# houz_bedroom.net
KiCad netlist of a schematic drawn in EAGLE
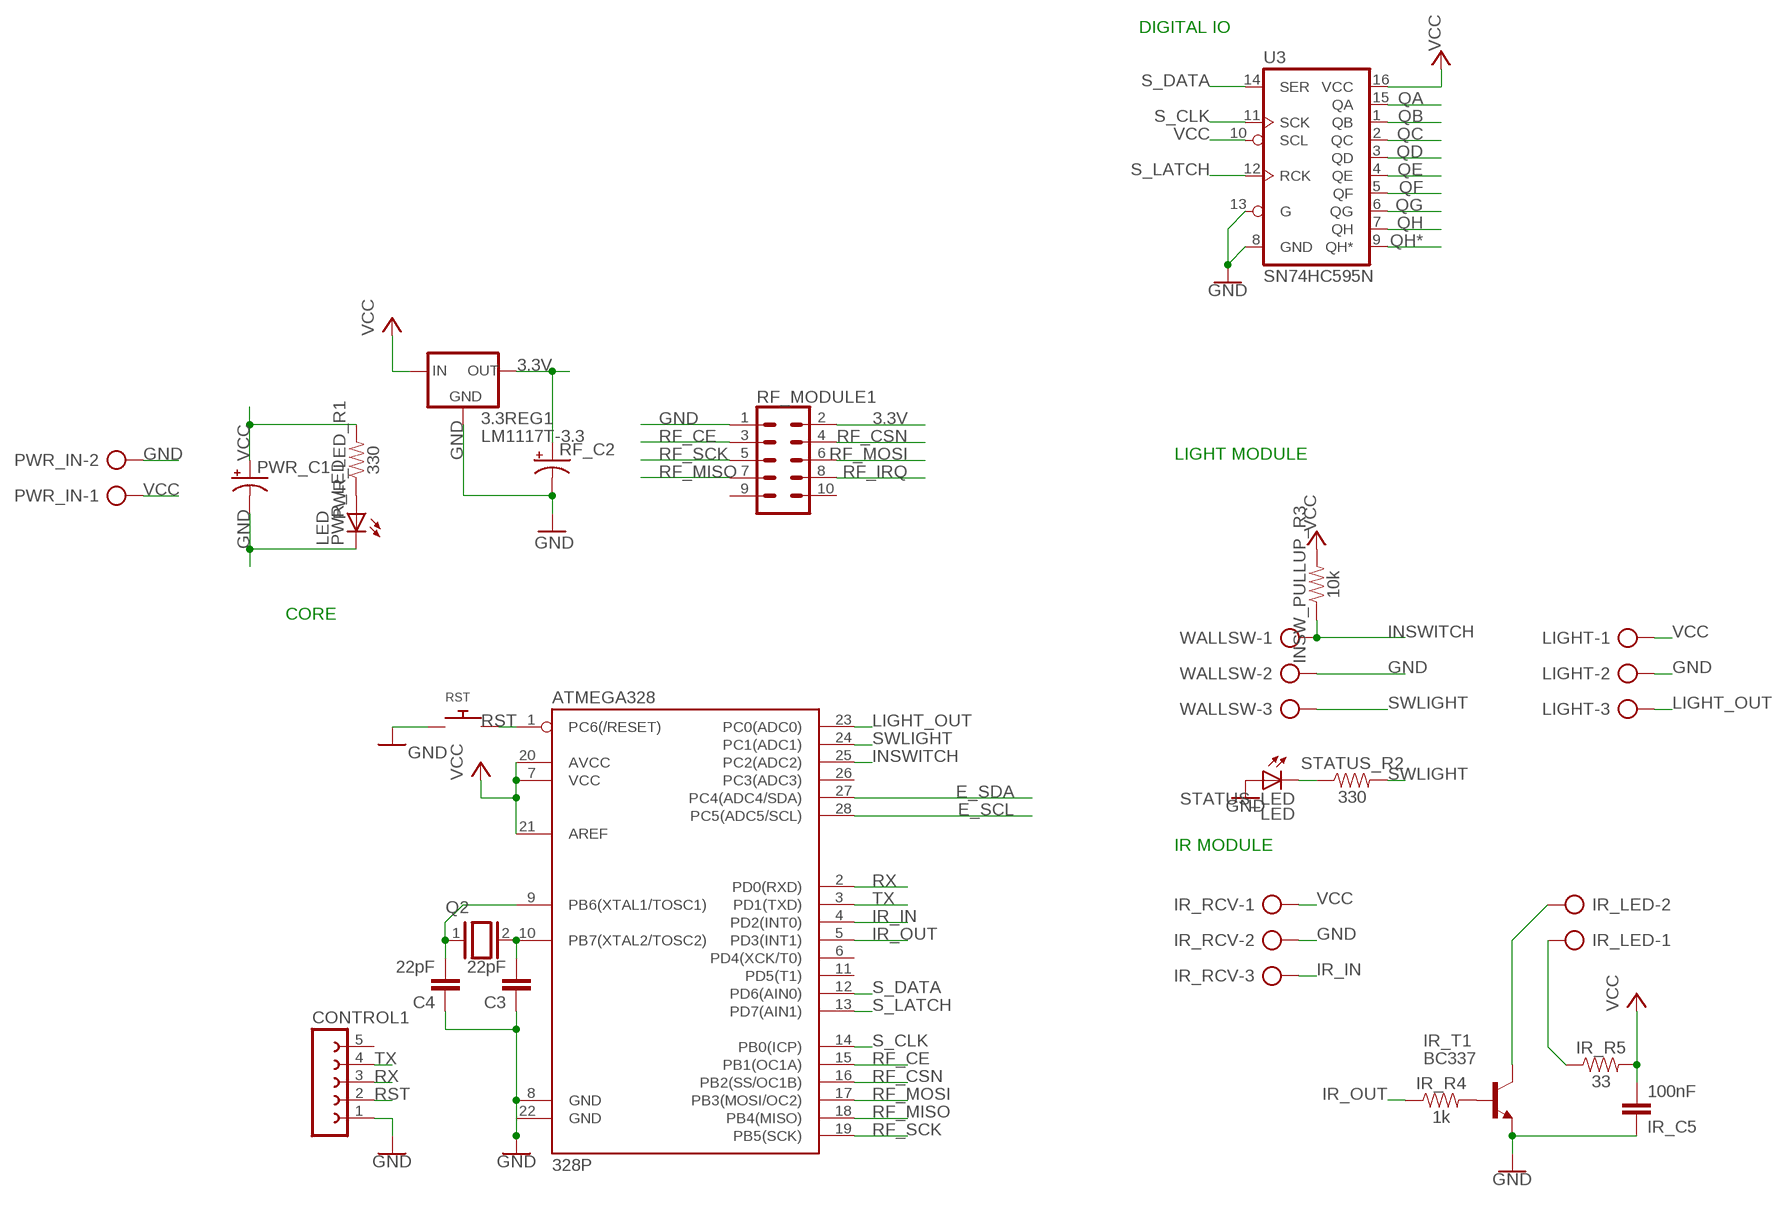
[diagram p0: schematic, sheet 1]

(export (version "E")
  (design (tool "Eeschema 10.0.6"))
  (components
    (comp (ref "3.3REG1")
      (value "LM1117T-3.3")
      (footprint "eagle-import:TO220")
      (libsource (lib "eagle-import") (part "LM1117T-3.3"))
    )
    (comp (ref "ATMEGA328")
      (value "328P")
      (footprint "eagle-import:DIP28")
      (libsource (lib "eagle-import") (part "ATMEGA328P_PDIP"))
    )
    (comp (ref "C3")
      (value "22pF")
      (footprint "eagle-import:C050-030X075")
      (libsource (lib "eagle-import") (part "C-EU050-030X075"))
    )
    (comp (ref "C4")
      (value "22pF")
      (footprint "eagle-import:C050-030X075")
      (libsource (lib "eagle-import") (part "C-EU050-030X075"))
    )
    (comp (ref "CONTROL1")
      (value "FE05-1")
      (footprint "eagle-import:FE05-1")
      (libsource (lib "eagle-import") (part "FE05-1"))
    )
    (comp (ref "INSW_PULLUP_R3")
      (value "10k")
      (footprint "eagle-import:AXIAL-0.3")
      (libsource (lib "eagle-import") (part "RESISTORAXIAL-0.3"))
    )
    (comp (ref "IR_C5")
      (value "100nF")
      (footprint "eagle-import:C050-030X075")
      (libsource (lib "eagle-import") (part "C-EU050-030X075"))
    )
    (comp (ref "IR_LED")
      (value "AK500/2-H")
      (footprint "eagle-import:AK500_2-H")
      (libsource (lib "eagle-import") (part "AK500/2-H"))
    )
    (comp (ref "IR_R4")
      (value "1k")
      (footprint "eagle-import:AXIAL-0.3")
      (libsource (lib "eagle-import") (part "RESISTORAXIAL-0.3"))
    )
    (comp (ref "IR_R5")
      (value "33")
      (footprint "eagle-import:AXIAL-0.3")
      (libsource (lib "eagle-import") (part "RESISTORAXIAL-0.3"))
    )
    (comp (ref "IR_RCV")
      (value "AK500/3")
      (footprint "eagle-import:AK500_3")
      (libsource (lib "eagle-import") (part "AK500/3"))
    )
    (comp (ref "IR_T1")
      (value "BC337")
      (footprint "eagle-import:TO92")
      (libsource (lib "eagle-import") (part "BC337"))
    )
    (comp (ref "LIGHT")
      (value "AK500/3")
      (footprint "eagle-import:AK500_3")
      (libsource (lib "eagle-import") (part "AK500/3"))
    )
    (comp (ref "PWR_C1")
      (value "CPOL-USE7.5-16")
      (footprint "eagle-import:E7,5-16")
      (libsource (lib "eagle-import") (part "CPOL-USE7.5-16"))
    )
    (comp (ref "PWR_IN")
      (value "AK500/2-H")
      (footprint "eagle-import:AK500_2-H")
      (libsource (lib "eagle-import") (part "AK500/2-H"))
    )
    (comp (ref "PWR_LED")
      (value "LED")
      (footprint "eagle-import:LED3MM")
      (libsource (lib "eagle-import") (part "LED3MM"))
    )
    (comp (ref "PWR_LED_R1")
      (value "330")
      (footprint "eagle-import:AXIAL-0.3")
      (libsource (lib "eagle-import") (part "RESISTORAXIAL-0.3"))
    )
    (comp (ref "Q2")
      (value "16MHz")
      (footprint "eagle-import:QS")
      (libsource (lib "eagle-import") (part "XTAL/S"))
    )
    (comp (ref "RF_C2")
      (value "CPOL-USE5-10.5")
      (footprint "eagle-import:E5-10,5")
      (libsource (lib "eagle-import") (part "CPOL-USE5-10.5"))
    )
    (comp (ref "RF_MODULE1")
      (value "CONN_05X2NO_SILK")
      (footprint "eagle-import:2X5_NOSILK")
      (libsource (lib "eagle-import") (part "CONN_05X2NO_SILK"))
    )
    (comp (ref "RST")
      (value "SWITCH_PUSHBUTTONEVQ-PE")
      (footprint "eagle-import:TACT_PANA-EVQ")
      (libsource (lib "eagle-import") (part "SWITCH_PUSHBUTTONEVQ-PE"))
    )
    (comp (ref "STATUS_LED")
      (value "LED")
      (footprint "eagle-import:LED3MM")
      (libsource (lib "eagle-import") (part "LED3MM"))
    )
    (comp (ref "STATUS_R2")
      (value "330")
      (footprint "eagle-import:AXIAL-0.3")
      (libsource (lib "eagle-import") (part "RESISTORAXIAL-0.3"))
    )
    (comp (ref "U3")
      (value "SN74HC595N")
      (footprint "eagle-import:DIP16")
      (libsource (lib "eagle-import") (part "74595NHC"))
    )
    (comp (ref "WALLSW")
      (value "AK500/3")
      (footprint "eagle-import:AK500_3")
      (libsource (lib "eagle-import") (part "AK500/3"))
    )
  )
  (nets
    (net (code "1") (name "/3.3V") (class "Default")
      (node (ref "3.3REG1") (pin "2") (pinfunction "OUT_2") (pintype "passive"))
      (node (ref "RF_C2") (pin "+") (pinfunction "+_+") (pintype "passive"))
      (node (ref "RF_MODULE1") (pin "2") (pinfunction "2_2") (pintype "passive"))
    )
    (net (code "2") (name "/E_SCL") (class "Default")
      (node (ref "ATMEGA328") (pin "28") (pinfunction "PC5(ADC5/SCL)_28") (pintype "bidirectional"))
    )
    (net (code "3") (name "/E_SDA") (class "Default")
      (node (ref "ATMEGA328") (pin "27") (pinfunction "PC4(ADC4/SDA)_27") (pintype "bidirectional"))
    )
    (net (code "4") (name "/INSWITCH") (class "Default")
      (node (ref "ATMEGA328") (pin "25") (pinfunction "PC2(ADC2)_25") (pintype "bidirectional"))
      (node (ref "INSW_PULLUP_R3") (pin "P$1") (pinfunction "1_P$1") (pintype "passive"))
      (node (ref "WALLSW") (pin "1") (pinfunction "KL_1") (pintype "passive"))
    )
    (net (code "5") (name "/IR_IN") (class "Default")
      (node (ref "ATMEGA328") (pin "4") (pinfunction "PD2(INT0)_4") (pintype "bidirectional"))
      (node (ref "IR_RCV") (pin "3") (pinfunction "KL_3") (pintype "passive"))
    )
    (net (code "6") (name "/IR_OUT") (class "Default")
      (node (ref "ATMEGA328") (pin "5") (pinfunction "PD3(INT1)_5") (pintype "bidirectional"))
      (node (ref "IR_R4") (pin "P$1") (pinfunction "1_P$1") (pintype "passive"))
    )
    (net (code "7") (name "/LIGHT_OUT") (class "Default")
      (node (ref "ATMEGA328") (pin "23") (pinfunction "PC0(ADC0)_23") (pintype "bidirectional"))
      (node (ref "LIGHT") (pin "3") (pinfunction "KL_3") (pintype "passive"))
    )
    (net (code "8") (name "/QA") (class "Default")
      (node (ref "U3") (pin "15") (pinfunction "QA_15") (pintype "tri_state"))
    )
    (net (code "9") (name "/QB") (class "Default")
      (node (ref "U3") (pin "1") (pinfunction "QB_1") (pintype "tri_state"))
    )
    (net (code "10") (name "/QC") (class "Default")
      (node (ref "U3") (pin "2") (pinfunction "QC_2") (pintype "tri_state"))
    )
    (net (code "11") (name "/QD") (class "Default")
      (node (ref "U3") (pin "3") (pinfunction "QD_3") (pintype "tri_state"))
    )
    (net (code "12") (name "/QE") (class "Default")
      (node (ref "U3") (pin "4") (pinfunction "QE_4") (pintype "tri_state"))
    )
    (net (code "13") (name "/QF") (class "Default")
      (node (ref "U3") (pin "5") (pinfunction "QF_5") (pintype "tri_state"))
    )
    (net (code "14") (name "/QG") (class "Default")
      (node (ref "U3") (pin "6") (pinfunction "QG_6") (pintype "tri_state"))
    )
    (net (code "15") (name "/QH") (class "Default")
      (node (ref "U3") (pin "7") (pinfunction "QH_7") (pintype "tri_state"))
    )
    (net (code "16") (name "/QH*") (class "Default")
      (node (ref "U3") (pin "9") (pinfunction "QH*_9") (pintype "tri_state"))
    )
    (net (code "17") (name "/RF_CE") (class "Default")
      (node (ref "ATMEGA328") (pin "15") (pinfunction "PB1(OC1A)_15") (pintype "bidirectional"))
      (node (ref "RF_MODULE1") (pin "3") (pinfunction "3_3") (pintype "passive"))
    )
    (net (code "18") (name "/RF_CSN") (class "Default")
      (node (ref "ATMEGA328") (pin "16") (pinfunction "PB2(SS/OC1B)_16") (pintype "bidirectional"))
      (node (ref "RF_MODULE1") (pin "4") (pinfunction "4_4") (pintype "passive"))
    )
    (net (code "19") (name "/RF_IRQ") (class "Default")
      (node (ref "RF_MODULE1") (pin "8") (pinfunction "8_8") (pintype "passive"))
    )
    (net (code "20") (name "/RF_MISO") (class "Default")
      (node (ref "ATMEGA328") (pin "18") (pinfunction "PB4(MISO)_18") (pintype "bidirectional"))
      (node (ref "RF_MODULE1") (pin "7") (pinfunction "7_7") (pintype "passive"))
    )
    (net (code "21") (name "/RF_MOSI") (class "Default")
      (node (ref "ATMEGA328") (pin "17") (pinfunction "PB3(MOSI/OC2)_17") (pintype "bidirectional"))
      (node (ref "RF_MODULE1") (pin "6") (pinfunction "6_6") (pintype "passive"))
    )
    (net (code "22") (name "/RF_SCK") (class "Default")
      (node (ref "ATMEGA328") (pin "19") (pinfunction "PB5(SCK)_19") (pintype "bidirectional"))
      (node (ref "RF_MODULE1") (pin "5") (pinfunction "5_5") (pintype "passive"))
    )
    (net (code "23") (name "/RST") (class "Default")
      (node (ref "ATMEGA328") (pin "1") (pinfunction "PC6(/RESET)_1") (pintype "bidirectional"))
      (node (ref "CONTROL1") (pin "2") (pinfunction "2_2") (pintype "passive"))
      (node (ref "RST") (pin "P$2") (pinfunction "P$2_P$2") (pintype "passive"))
    )
    (net (code "24") (name "/RX") (class "Default")
      (node (ref "ATMEGA328") (pin "2") (pinfunction "PD0(RXD)_2") (pintype "bidirectional"))
      (node (ref "CONTROL1") (pin "3") (pinfunction "3_3") (pintype "passive"))
    )
    (net (code "25") (name "/SWLIGHT") (class "Default")
      (node (ref "ATMEGA328") (pin "24") (pinfunction "PC1(ADC1)_24") (pintype "bidirectional"))
      (node (ref "STATUS_R2") (pin "P$2") (pinfunction "2_P$2") (pintype "passive"))
      (node (ref "WALLSW") (pin "3") (pinfunction "KL_3") (pintype "passive"))
    )
    (net (code "26") (name "/S_CLK") (class "Default")
      (node (ref "ATMEGA328") (pin "14") (pinfunction "PB0(ICP)_14") (pintype "bidirectional"))
      (node (ref "U3") (pin "11") (pinfunction "SCK_11") (pintype "input"))
    )
    (net (code "27") (name "/S_DATA") (class "Default")
      (node (ref "ATMEGA328") (pin "12") (pinfunction "PD6(AIN0)_12") (pintype "bidirectional"))
      (node (ref "U3") (pin "14") (pinfunction "SER_14") (pintype "input"))
    )
    (net (code "28") (name "/S_LATCH") (class "Default")
      (node (ref "ATMEGA328") (pin "13") (pinfunction "PD7(AIN1)_13") (pintype "bidirectional"))
      (node (ref "U3") (pin "12") (pinfunction "RCK_12") (pintype "input"))
    )
    (net (code "29") (name "/TX") (class "Default")
      (node (ref "ATMEGA328") (pin "3") (pinfunction "PD1(TXD)_3") (pintype "bidirectional"))
      (node (ref "CONTROL1") (pin "4") (pinfunction "4_4") (pintype "passive"))
    )
    (net (code "30") (name "GND") (class "Default")
      (node (ref "3.3REG1") (pin "1") (pinfunction "GND_1") (pintype "input"))
      (node (ref "ATMEGA328") (pin "22") (pinfunction "GND_22") (pintype "bidirectional"))
      (node (ref "ATMEGA328") (pin "8") (pinfunction "GND_8") (pintype "bidirectional"))
      (node (ref "C3") (pin "1") (pinfunction "1_1") (pintype "passive"))
      (node (ref "C4") (pin "1") (pinfunction "1_1") (pintype "passive"))
      (node (ref "CONTROL1") (pin "1") (pinfunction "1_1") (pintype "passive"))
      (node (ref "IR_C5") (pin "1") (pinfunction "1_1") (pintype "passive"))
      (node (ref "IR_RCV") (pin "2") (pinfunction "KL_2") (pintype "passive"))
      (node (ref "IR_T1") (pin "1") (pinfunction "E_1") (pintype "passive"))
      (node (ref "LIGHT") (pin "2") (pinfunction "KL_2") (pintype "passive"))
      (node (ref "PWR_C1") (pin "-") (pinfunction "-_-") (pintype "passive"))
      (node (ref "PWR_IN") (pin "2") (pinfunction "KL_2") (pintype "passive"))
      (node (ref "PWR_LED") (pin "K") (pinfunction "C_K") (pintype "passive"))
      (node (ref "RF_C2") (pin "-") (pinfunction "-_-") (pintype "passive"))
      (node (ref "RF_MODULE1") (pin "1") (pinfunction "1_1") (pintype "passive"))
      (node (ref "RST") (pin "P$1") (pinfunction "P$1_P$1") (pintype "passive"))
      (node (ref "STATUS_LED") (pin "A") (pinfunction "A_A") (pintype "passive"))
      (node (ref "U3") (pin "13") (pinfunction "G_13") (pintype "input"))
      (node (ref "U3") (pin "8") (pinfunction "GND_8") (pintype "power_in"))
      (node (ref "WALLSW") (pin "2") (pinfunction "KL_2") (pintype "passive"))
    )
    (net (code "31") (name "Net-(ATMEGA328-PB6(XTAL1{slash}TOSC1))") (class "Default")
      (node (ref "ATMEGA328") (pin "9") (pinfunction "PB6(XTAL1/TOSC1)_9") (pintype "bidirectional"))
      (node (ref "C4") (pin "2") (pinfunction "2_2") (pintype "passive"))
      (node (ref "Q2") (pin "1") (pinfunction "1_1") (pintype "passive"))
    )
    (net (code "32") (name "Net-(ATMEGA328-PB7(XTAL2{slash}TOSC2))") (class "Default")
      (node (ref "ATMEGA328") (pin "10") (pinfunction "PB7(XTAL2/TOSC2)_10") (pintype "bidirectional"))
      (node (ref "C3") (pin "2") (pinfunction "2_2") (pintype "passive"))
      (node (ref "Q2") (pin "2") (pinfunction "2_2") (pintype "passive"))
    )
    (net (code "33") (name "Net-(IR_LEDA-KL)") (class "Default")
      (node (ref "IR_LED") (pin "1") (pinfunction "KL_1") (pintype "passive"))
      (node (ref "IR_R5") (pin "P$1") (pinfunction "1_P$1") (pintype "passive"))
    )
    (net (code "34") (name "Net-(IR_LEDB-KL)") (class "Default")
      (node (ref "IR_LED") (pin "2") (pinfunction "KL_2") (pintype "passive"))
      (node (ref "IR_T1") (pin "3") (pinfunction "C_3") (pintype "passive"))
    )
    (net (code "35") (name "Net-(IR_R4-2)") (class "Default")
      (node (ref "IR_R4") (pin "P$2") (pinfunction "2_P$2") (pintype "passive"))
      (node (ref "IR_T1") (pin "2") (pinfunction "B_2") (pintype "passive"))
    )
    (net (code "36") (name "Net-(PWR_LED_R1-1)") (class "Default")
      (node (ref "PWR_LED") (pin "A") (pinfunction "A_A") (pintype "passive"))
      (node (ref "PWR_LED_R1") (pin "P$1") (pinfunction "1_P$1") (pintype "passive"))
    )
    (net (code "37") (name "Net-(STATUS_LED-C)") (class "Default")
      (node (ref "STATUS_LED") (pin "K") (pinfunction "C_K") (pintype "passive"))
      (node (ref "STATUS_R2") (pin "P$1") (pinfunction "1_P$1") (pintype "passive"))
    )
    (net (code "38") (name "VCC") (class "Default")
      (node (ref "3.3REG1") (pin "3") (pinfunction "IN_3") (pintype "input"))
      (node (ref "ATMEGA328") (pin "20") (pinfunction "AVCC_20") (pintype "bidirectional"))
      (node (ref "ATMEGA328") (pin "21") (pinfunction "AREF_21") (pintype "bidirectional"))
      (node (ref "ATMEGA328") (pin "7") (pinfunction "VCC_7") (pintype "bidirectional"))
      (node (ref "INSW_PULLUP_R3") (pin "P$2") (pinfunction "2_P$2") (pintype "passive"))
      (node (ref "IR_C5") (pin "2") (pinfunction "2_2") (pintype "passive"))
      (node (ref "IR_R5") (pin "P$2") (pinfunction "2_P$2") (pintype "passive"))
      (node (ref "IR_RCV") (pin "1") (pinfunction "KL_1") (pintype "passive"))
      (node (ref "LIGHT") (pin "1") (pinfunction "KL_1") (pintype "passive"))
      (node (ref "PWR_C1") (pin "+") (pinfunction "+_+") (pintype "passive"))
      (node (ref "PWR_IN") (pin "1") (pinfunction "KL_1") (pintype "passive"))
      (node (ref "PWR_LED_R1") (pin "P$2") (pinfunction "2_P$2") (pintype "passive"))
      (node (ref "U3") (pin "10") (pinfunction "SCL_10") (pintype "input"))
      (node (ref "U3") (pin "16") (pinfunction "VCC_16") (pintype "power_in"))
    )
    (net (code "39") (name "unconnected-(ATMEGA328-PC3(ADC3)-Pad26)") (class "Default")
      (node (ref "ATMEGA328") (pin "26") (pinfunction "PC3(ADC3)_26") (pintype "bidirectional"))
    )
    (net (code "40") (name "unconnected-(ATMEGA328-PD4(XCK{slash}T0)-Pad6)") (class "Default")
      (node (ref "ATMEGA328") (pin "6") (pinfunction "PD4(XCK/T0)_6") (pintype "bidirectional"))
    )
    (net (code "41") (name "unconnected-(ATMEGA328-PD5(T1)-Pad11)") (class "Default")
      (node (ref "ATMEGA328") (pin "11") (pinfunction "PD5(T1)_11") (pintype "bidirectional"))
    )
    (net (code "42") (name "unconnected-(CONTROL1-Pad5)") (class "Default")
      (node (ref "CONTROL1") (pin "5") (pinfunction "5_5") (pintype "passive"))
    )
    (net (code "43") (name "unconnected-(RF_MODULE1-Pad9)") (class "Default")
      (node (ref "RF_MODULE1") (pin "9") (pinfunction "9_9") (pintype "passive"))
    )
    (net (code "44") (name "unconnected-(RF_MODULE1-Pad10)") (class "Default")
      (node (ref "RF_MODULE1") (pin "10") (pinfunction "10_10") (pintype "passive"))
    )
  )
)
